# RS485_v1.net
KiCad netlist of a schematic drawn in EAGLE
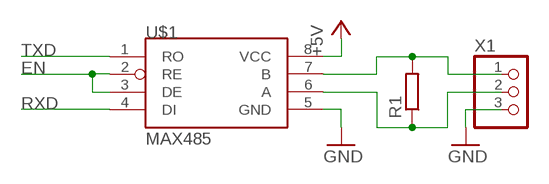
[diagram p0: schematic, sheet 1]

(export (version "E")
  (design (tool "Eeschema 10.0.6"))
  (components
    (comp (ref "R1")
      (value "R-EU_R0805")
      (footprint "eagle-import:R0805")
      (libsource (lib "eagle-import") (part "R-EU_R0805"))
    )
    (comp (ref "U$1")
      (value "MAX485")
      (footprint "eagle-import:SO08")
      (libsource (lib "eagle-import") (part "MAX485"))
    )
    (comp (ref "X1")
      (value "W237-103")
      (footprint "eagle-import:W237-103")
      (libsource (lib "eagle-import") (part "W237-103"))
    )
  )
  (nets
    (net (code "1") (name "+5V") (class "Default")
      (node (ref "U$1") (pin "8") (pinfunction "VCC_8") (pintype "bidirectional"))
    )
    (net (code "2") (name "/EN") (class "Default")
      (node (ref "U$1") (pin "2") (pinfunction "RE_2") (pintype "bidirectional"))
      (node (ref "U$1") (pin "3") (pinfunction "DE_3") (pintype "bidirectional"))
    )
    (net (code "3") (name "/RXD") (class "Default")
      (node (ref "U$1") (pin "4") (pinfunction "DI_4") (pintype "bidirectional"))
    )
    (net (code "4") (name "/TXD") (class "Default")
      (node (ref "U$1") (pin "1") (pinfunction "RO_1") (pintype "bidirectional"))
    )
    (net (code "5") (name "GND") (class "Default")
      (node (ref "U$1") (pin "5") (pinfunction "GND_5") (pintype "bidirectional"))
      (node (ref "X1") (pin "3") (pinfunction "3_3") (pintype "passive"))
    )
    (net (code "6") (name "Net-(U$1-A)") (class "Default")
      (node (ref "R1") (pin "1") (pinfunction "1_1") (pintype "passive"))
      (node (ref "U$1") (pin "6") (pinfunction "A_6") (pintype "bidirectional"))
      (node (ref "X1") (pin "2") (pinfunction "2_2") (pintype "passive"))
    )
    (net (code "7") (name "Net-(U$1-B)") (class "Default")
      (node (ref "R1") (pin "2") (pinfunction "2_2") (pintype "passive"))
      (node (ref "U$1") (pin "7") (pinfunction "B_7") (pintype "bidirectional"))
      (node (ref "X1") (pin "1") (pinfunction "1_1") (pintype "passive"))
    )
  )
)
